# MPU6050.net
KiCad netlist of a schematic drawn in Altium Designer
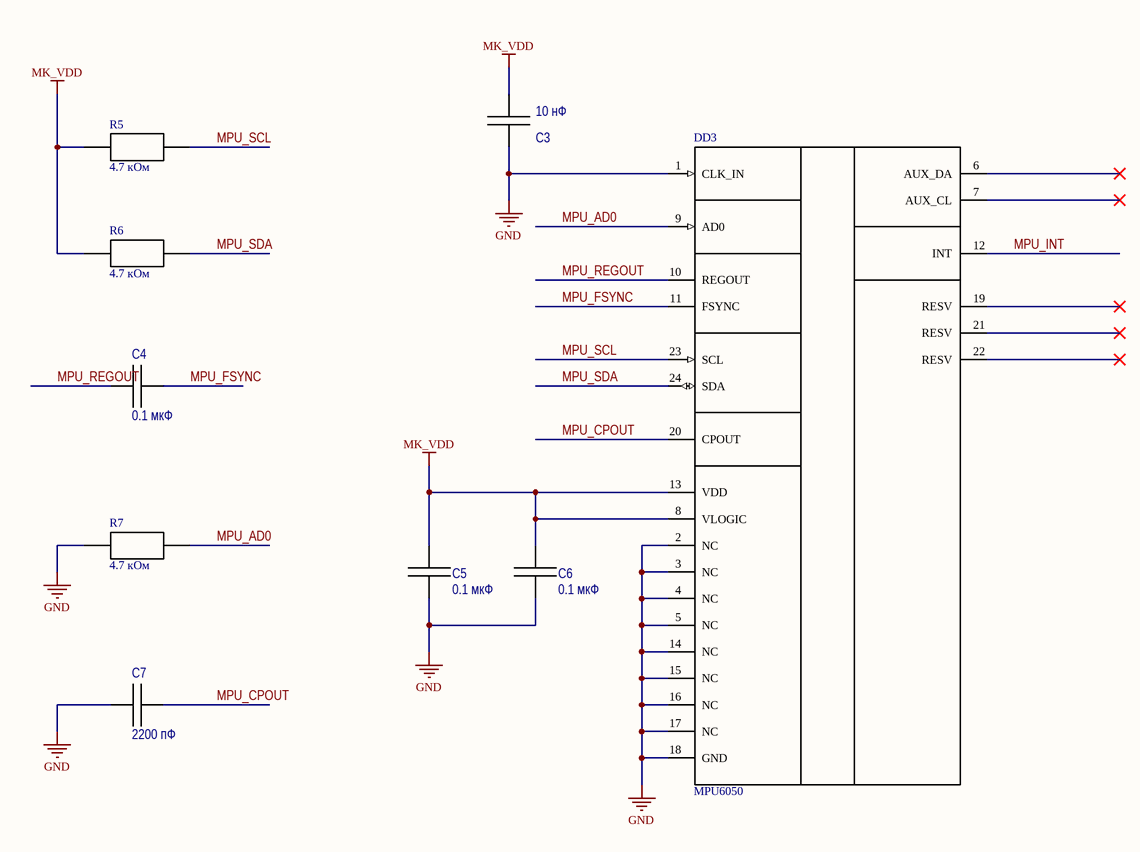
[diagram p0: MPU6050.SchDoc]

(export (version "E")
  (design (tool "Eeschema 10.0.6"))
  (components
    (comp (ref "C3")
      (value "10 нФ")
      (footprint "C 1206")
      (description "SMD Capacitor 1206")
      (fields
        (field (name "TOLERANCE") "/Укажите допуск в процентах/")
        (field (name "MANUFACTURER") "/Укажите компанию-производителя/")
      )
      (libsource (lib "my_lib") (part "CAP 1206"))
    )
    (comp (ref "C4")
      (value "0.1 мкФ")
      (footprint "C 1206")
      (description "SMD Capacitor 1206")
      (fields
        (field (name "TOLERANCE") "/Укажите допуск в процентах/")
        (field (name "MANUFACTURER") "/Укажите компанию-производителя/")
      )
      (libsource (lib "my_lib") (part "CAP 1206"))
    )
    (comp (ref "C5")
      (value "0.1 мкФ")
      (footprint "C 1206")
      (description "SMD Capacitor 1206")
      (fields
        (field (name "TOLERANCE") "/Укажите допуск в процентах/")
        (field (name "MANUFACTURER") "/Укажите компанию-производителя/")
      )
      (libsource (lib "my_lib") (part "CAP 1206"))
    )
    (comp (ref "C6")
      (value "0.1 мкФ")
      (footprint "C 1206")
      (description "SMD Capacitor 1206")
      (fields
        (field (name "TOLERANCE") "/Укажите допуск в процентах/")
        (field (name "MANUFACTURER") "/Укажите компанию-производителя/")
      )
      (libsource (lib "my_lib") (part "CAP 1206"))
    )
    (comp (ref "C7")
      (value "2200 пФ")
      (footprint "C 1206")
      (description "SMD Capacitor 1206")
      (fields
        (field (name "TOLERANCE") "/Укажите допуск в процентах/")
        (field (name "MANUFACTURER") "/Укажите компанию-производителя/")
      )
      (libsource (lib "my_lib") (part "CAP 1206"))
    )
    (comp (ref "DD3")
      (value "MPU6050")
      (footprint "QFN50P400X400X95_HS-25N")
      (libsource (lib "my_lib") (part "MPU6050"))
    )
    (comp (ref "R5") (value "4.7 кОм") (footprint "RES 0805") (libsource (lib "my_lib") (part "RES 0805")))
    (comp (ref "R6") (value "4.7 кОм") (footprint "RES 0805") (libsource (lib "my_lib") (part "RES 0805")))
    (comp (ref "R7") (value "4.7 кОм") (footprint "RES 0805") (libsource (lib "my_lib") (part "RES 0805")))
  )
  (nets
    (net (code "1") (name "/MPU_AD0") (class "Default")
      (node (ref "DD3") (pin "9") (pinfunction "AD0_9") (pintype "input"))
      (node (ref "R7") (pin "1") (pinfunction "1_1") (pintype "passive"))
    )
    (net (code "2") (name "/MPU_CPOUT") (class "Default")
      (node (ref "C7") (pin "2") (pinfunction "2_2") (pintype "passive"))
      (node (ref "DD3") (pin "20") (pinfunction "CPOUT_20") (pintype "passive"))
    )
    (net (code "3") (name "/MPU_FSYNC") (class "Default")
      (node (ref "C4") (pin "2") (pinfunction "2_2") (pintype "passive"))
      (node (ref "DD3") (pin "11") (pinfunction "FSYNC_11") (pintype "passive"))
    )
    (net (code "4") (name "/MPU_INT") (class "Default")
      (node (ref "DD3") (pin "12") (pinfunction "INT_12") (pintype "open_collector"))
    )
    (net (code "5") (name "/MPU_REGOUT") (class "Default")
      (node (ref "C4") (pin "1") (pinfunction "1_1") (pintype "passive"))
      (node (ref "DD3") (pin "10") (pinfunction "REGOUT_10") (pintype "passive"))
    )
    (net (code "6") (name "/MPU_SCL") (class "Default")
      (node (ref "DD3") (pin "23") (pinfunction "SCL_23") (pintype "input"))
      (node (ref "R5") (pin "1") (pinfunction "1_1") (pintype "passive"))
    )
    (net (code "7") (name "/MPU_SDA") (class "Default")
      (node (ref "DD3") (pin "24") (pinfunction "SDA_24") (pintype "bidirectional"))
      (node (ref "R6") (pin "1") (pinfunction "1_1") (pintype "passive"))
    )
    (net (code "8") (name "GND") (class "Default")
      (node (ref "C3") (pin "1") (pinfunction "1_1") (pintype "passive"))
      (node (ref "C5") (pin "2") (pinfunction "2_2") (pintype "passive"))
      (node (ref "C6") (pin "2") (pinfunction "2_2") (pintype "passive"))
      (node (ref "C7") (pin "1") (pinfunction "1_1") (pintype "passive"))
      (node (ref "DD3") (pin "1") (pinfunction "CLK_IN_1") (pintype "input"))
      (node (ref "DD3") (pin "14") (pinfunction "NC_14") (pintype "passive"))
      (node (ref "DD3") (pin "15") (pinfunction "NC_15") (pintype "passive"))
      (node (ref "DD3") (pin "16") (pinfunction "NC_16") (pintype "passive"))
      (node (ref "DD3") (pin "17") (pinfunction "NC_17") (pintype "passive"))
      (node (ref "DD3") (pin "18") (pinfunction "GND_18") (pintype "power_in"))
      (node (ref "DD3") (pin "2") (pinfunction "NC_2") (pintype "passive"))
      (node (ref "DD3") (pin "3") (pinfunction "NC_3") (pintype "passive"))
      (node (ref "DD3") (pin "4") (pinfunction "NC_4") (pintype "passive"))
      (node (ref "DD3") (pin "5") (pinfunction "NC_5") (pintype "passive"))
      (node (ref "R7") (pin "2") (pinfunction "2_2") (pintype "passive"))
    )
    (net (code "9") (name "MK_VDD") (class "Default")
      (node (ref "C3") (pin "2") (pinfunction "2_2") (pintype "passive"))
      (node (ref "C5") (pin "1") (pinfunction "1_1") (pintype "passive"))
      (node (ref "C6") (pin "1") (pinfunction "1_1") (pintype "passive"))
      (node (ref "DD3") (pin "13") (pinfunction "VDD_13") (pintype "power_in"))
      (node (ref "DD3") (pin "8") (pinfunction "VLOGIC_8") (pintype "power_in"))
      (node (ref "R5") (pin "2") (pinfunction "2_2") (pintype "passive"))
      (node (ref "R6") (pin "2") (pinfunction "2_2") (pintype "passive"))
    )
    (net (code "10") (name "unconnected-(DD3-AUX_CL-Pad7)") (class "Default")
      (node (ref "DD3") (pin "7") (pinfunction "AUX_CL_7") (pintype "passive+no_connect"))
    )
    (net (code "11") (name "unconnected-(DD3-AUX_DA-Pad6)") (class "Default")
      (node (ref "DD3") (pin "6") (pinfunction "AUX_DA_6") (pintype "passive+no_connect"))
    )
    (net (code "12") (name "unconnected-(DD3-RESV-Pad19)") (class "Default")
      (node (ref "DD3") (pin "19") (pinfunction "RESV_19") (pintype "passive+no_connect"))
    )
    (net (code "13") (name "unconnected-(DD3-RESV-Pad21)") (class "Default")
      (node (ref "DD3") (pin "21") (pinfunction "RESV_21") (pintype "passive+no_connect"))
    )
    (net (code "14") (name "unconnected-(DD3-RESV-Pad22)") (class "Default")
      (node (ref "DD3") (pin "22") (pinfunction "RESV_22") (pintype "passive+no_connect"))
    )
  )
)
